# Motor-Y.net
KiCad netlist of a schematic drawn in Altium Designer
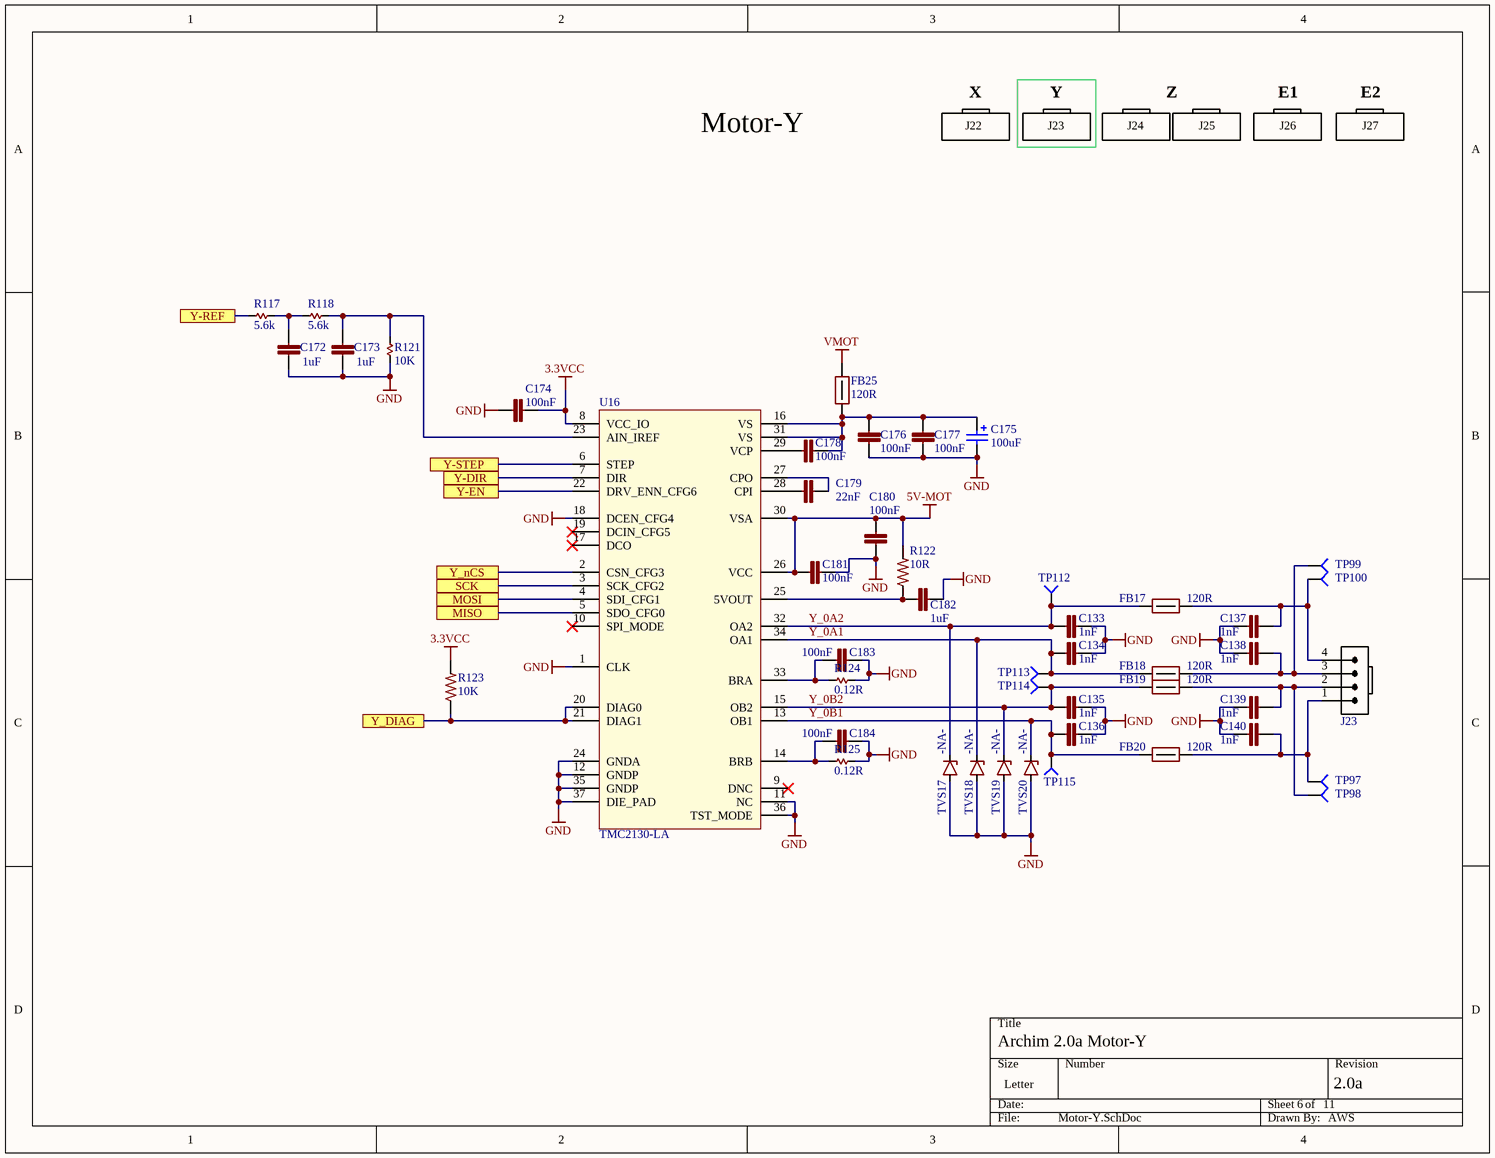
[diagram p0: Motor-Y.SchDoc]

(export (version "E")
  (design (tool "Eeschema 10.0.6"))
  (components
    (comp (ref "C133")
      (value "1nF")
      (footprint "C0402")
      (description "1000pF 50V Ceramic Capacitor X7R 0402 (1005 Metric) 0.039\" L x 0.020\" W (1.00mm x 0.50mm)")
      (fields (field (name "MANUFACTURER") "Murata") (field (name "PART") "1nF 50V X7R 0402"))
      (libsource (lib "3Delight") (part "CAP 1nF 50V 0402 X7R"))
    )
    (comp (ref "C134")
      (value "1nF")
      (footprint "C0402")
      (description "1000pF 50V Ceramic Capacitor X7R 0402 (1005 Metric) 0.039\" L x 0.020\" W (1.00mm x 0.50mm)")
      (fields (field (name "MANUFACTURER") "Murata") (field (name "PART") "1nF 50V X7R 0402"))
      (libsource (lib "3Delight") (part "CAP 1nF 50V 0402 X7R"))
    )
    (comp (ref "C135")
      (value "1nF")
      (footprint "C0402")
      (description "1000pF 50V Ceramic Capacitor X7R 0402 (1005 Metric) 0.039\" L x 0.020\" W (1.00mm x 0.50mm)")
      (fields (field (name "MANUFACTURER") "Murata") (field (name "PART") "1nF 50V X7R 0402"))
      (libsource (lib "3Delight") (part "CAP 1nF 50V 0402 X7R"))
    )
    (comp (ref "C136")
      (value "1nF")
      (footprint "C0402")
      (description "1000pF 50V Ceramic Capacitor X7R 0402 (1005 Metric) 0.039\" L x 0.020\" W (1.00mm x 0.50mm)")
      (fields (field (name "MANUFACTURER") "Murata") (field (name "PART") "1nF 50V X7R 0402"))
      (libsource (lib "3Delight") (part "CAP 1nF 50V 0402 X7R"))
    )
    (comp (ref "C137")
      (value "1nF")
      (footprint "C0402")
      (description "1000pF 50V Ceramic Capacitor X7R 0402 (1005 Metric) 0.039\" L x 0.020\" W (1.00mm x 0.50mm)")
      (fields (field (name "MANUFACTURER") "Murata") (field (name "PART") "1nF 50V X7R 0402"))
      (libsource (lib "") (part "CAP 1nF 50V 0402 X7R_1"))
    )
    (comp (ref "C138")
      (value "1nF")
      (footprint "C0402")
      (description "1000pF 50V Ceramic Capacitor X7R 0402 (1005 Metric) 0.039\" L x 0.020\" W (1.00mm x 0.50mm)")
      (fields (field (name "MANUFACTURER") "Murata") (field (name "PART") "1nF 50V X7R 0402"))
      (libsource (lib "") (part "CAP 1nF 50V 0402 X7R_1"))
    )
    (comp (ref "C139")
      (value "1nF")
      (footprint "C0402")
      (description "1000pF 50V Ceramic Capacitor X7R 0402 (1005 Metric) 0.039\" L x 0.020\" W (1.00mm x 0.50mm)")
      (fields (field (name "MANUFACTURER") "Murata") (field (name "PART") "1nF 50V X7R 0402"))
      (libsource (lib "") (part "CAP 1nF 50V 0402 X7R_1"))
    )
    (comp (ref "C140")
      (value "1nF")
      (footprint "C0402")
      (description "1000pF 50V Ceramic Capacitor X7R 0402 (1005 Metric) 0.039\" L x 0.020\" W (1.00mm x 0.50mm)")
      (fields (field (name "MANUFACTURER") "Murata") (field (name "PART") "1nF 50V X7R 0402"))
      (libsource (lib "") (part "CAP 1nF 50V 0402 X7R_1"))
    )
    (comp (ref "C172")
      (value "1uF")
      (footprint "C0402")
      (description "CAP CER 0402 1uF 6.3V 10% X5R")
      (fields (field (name "MANUFACTURER") "Murata") (field (name "PART") "1uF 6.3V X5R 0402"))
      (libsource (lib "3Delight") (part "GRM155R60J105KE19D"))
    )
    (comp (ref "C173")
      (value "1uF")
      (footprint "C0402")
      (description "CAP CER 0402 1uF 6.3V 10% X5R")
      (fields (field (name "MANUFACTURER") "Murata") (field (name "PART") "1uF 6.3V X5R 0402"))
      (libsource (lib "3Delight") (part "GRM155R60J105KE19D"))
    )
    (comp (ref "C174")
      (value "100nF")
      (footprint "C0402")
      (description "CAP CER 0402 100nF 16V 10% X7R")
      (fields (field (name "MANUFACTURER") "Murata") (field (name "PART") "0.1uF 16V X7R 0402"))
      (libsource (lib "3Delight") (part "GRM155R71C104KA88D"))
    )
    (comp (ref "C175")
      (value "100uF")
      (footprint "CAP-ELEC-063063077")
      (description "CAP ALUM 100UF 35V 20% SMD")
      (fields (field (name "MANUFACTURER") "Nichicon") (field (name "PART") "100uF 35V SMD Al-El"))
      (libsource (lib "3Delight") (part "UWT1V101MCL1GS"))
    )
    (comp (ref "C176")
      (value "100nF")
      (footprint "C0603")
      (description "CAP CER 0603 100nF 50V 10% X7R")
      (fields (field (name "MANUFACTURER") "Kemet") (field (name "PART") "100nF 50V X7R 0603"))
      (libsource (lib "3Delight") (part "C0603C104K5RACTU"))
    )
    (comp (ref "C177")
      (value "100nF")
      (footprint "C0603")
      (description "CAP CER 0603 100nF 50V 10% X7R")
      (fields (field (name "MANUFACTURER") "Kemet") (field (name "PART") "100nF 50V X7R 0603"))
      (libsource (lib "3Delight") (part "C0603C104K5RACTU"))
    )
    (comp (ref "C178")
      (value "100nF")
      (footprint "C0603")
      (description "CAP CER 0603 100nF 50V 10% X7R")
      (fields (field (name "MANUFACTURER") "Kemet") (field (name "PART") "100nF 50V X7R 0603"))
      (libsource (lib "") (part "C0603C104K5RACTU_2"))
    )
    (comp (ref "C179")
      (value "22nF")
      (footprint "C0402")
      (description "CAP CER 0402 22nF ±10% 50V X7R")
      (fields (field (name "MANUFACTURER") "YAGEO") (field (name "TOLERANCE") "+/- 10%"))
      (libsource (lib "3Delight") (part "GCM155R71H223KA55D"))
    )
    (comp (ref "C180")
      (value "100nF")
      (footprint "C0402")
      (description "CAP CER 0402 100nF 16V 10% X7R")
      (fields (field (name "MANUFACTURER") "Murata") (field (name "PART") "0.1uF 16V X7R 0402"))
      (libsource (lib "") (part "GRM155R71C104KA88D_1"))
    )
    (comp (ref "C181")
      (value "100nF")
      (footprint "C0402")
      (description "CAP CER 0402 100nF 16V 10% X7R")
      (fields (field (name "MANUFACTURER") "Murata") (field (name "PART") "0.1uF 16V X7R 0402"))
      (libsource (lib "3Delight") (part "GRM155R71C104KA88D"))
    )
    (comp (ref "C182")
      (value "1uF")
      (footprint "C0402")
      (description "CAP CER 0402 1uF 6.3V 10% X5R")
      (fields (field (name "MANUFACTURER") "Murata") (field (name "PART") "1uF 6.3V X5R 0402"))
      (libsource (lib "") (part "GRM155R60J105KE19D_1"))
    )
    (comp (ref "C183")
      (value "100nF")
      (footprint "C0603")
      (description "CAP CER 0603 100nF 50V 10% X7R")
      (fields (field (name "MANUFACTURER") "Kemet") (field (name "PART") "100nF 50V X7R 0603"))
      (libsource (lib "") (part "C0603C104K5RACTU_1"))
    )
    (comp (ref "C184")
      (value "100nF")
      (footprint "C0603")
      (description "CAP CER 0603 100nF 50V 10% X7R")
      (fields (field (name "MANUFACTURER") "Kemet") (field (name "PART") "100nF 50V X7R 0603"))
      (libsource (lib "") (part "C0603C104K5RACTU_1"))
    )
    (comp (ref "FB17")
      (value "120R")
      (footprint "FB0603")
      (description "FERRITE BEAD 120 OHM 0603 1LN")
      (fields (field (name "MANUFACTURER") "Samsung") (field (name "PART") "FERRITE 120R 3A 0603"))
      (libsource (lib "3Delight") (part "FERRITE 220R 2.5A 0603"))
    )
    (comp (ref "FB18")
      (value "120R")
      (footprint "FB0603")
      (description "FERRITE BEAD 120 OHM 0603 1LN")
      (fields (field (name "MANUFACTURER") "Samsung") (field (name "PART") "FERRITE 120R 3A 0603"))
      (libsource (lib "3Delight") (part "FERRITE 220R 2.5A 0603"))
    )
    (comp (ref "FB19")
      (value "120R")
      (footprint "FB0603")
      (description "FERRITE BEAD 120 OHM 0603 1LN")
      (fields (field (name "MANUFACTURER") "Samsung") (field (name "PART") "FERRITE 120R 3A 0603"))
      (libsource (lib "3Delight") (part "FERRITE 220R 2.5A 0603"))
    )
    (comp (ref "FB20")
      (value "120R")
      (footprint "FB0603")
      (description "FERRITE BEAD 120 OHM 0603 1LN")
      (fields (field (name "MANUFACTURER") "Samsung") (field (name "PART") "FERRITE 120R 3A 0603"))
      (libsource (lib "3Delight") (part "FERRITE 220R 2.5A 0603"))
    )
    (comp (ref "FB25")
      (value "120R")
      (footprint "FB0603")
      (description "FERRITE BEAD 120 OHM 0603 1LN")
      (fields (field (name "MANUFACTURER") "Samsung") (field (name "PART") "FERRITE 120R 3A 0603"))
      (libsource (lib "Inductors") (part "FERRITE 120R 3A 0603"))
    )
    (comp (ref "J23")
      (value "Molex 0705430038")
      (footprint "4POL254 PIN-IN-PASTE")
      (description "Molex 4 Pin Clip Connector - Pin In Paste footprint")
      (libsource (lib "Connectors") (part "Molex 0705430003 PIP"))
    )
    (comp (ref "R117")
      (value "5.6k")
      (footprint "R0402")
      (description "RES SMD 5.6K OHM 1% 1/16W 0402")
      (fields (field (name "MANUFACTURER") "YAGEO") (field (name "TOLERANCE") "1%"))
      (libsource (lib "Resistors") (part "5.6k 1% 0402"))
    )
    (comp (ref "R118")
      (value "5.6k")
      (footprint "R0402")
      (description "RES SMD 5.6K OHM 1% 1/16W 0402")
      (fields (field (name "MANUFACTURER") "YAGEO") (field (name "TOLERANCE") "1%"))
      (libsource (lib "Resistors") (part "5.6k 1% 0402"))
    )
    (comp (ref "R121")
      (value "10K")
      (footprint "R0402")
      (description "RES SMD 10K OHM 1% 1/16W 0402")
      (fields (field (name "MANUFACTURER") "Yageo") (field (name "PART") "10k 1% 0402"))
      (libsource (lib "Resistors") (part "10k 1% 0402"))
    )
    (comp (ref "R122")
      (value "10R")
      (footprint "R0402")
      (description "RES SMD 10 OHM 1% 1/16W 0402")
      (fields (field (name "MANUFACTURER") "Yageo") (field (name "TOLERANCE") "1%"))
      (libsource (lib "3Delight") (part "RC0402FR-0710RL"))
    )
    (comp (ref "R123")
      (value "10K")
      (footprint "R0402")
      (description "RES SMD 10K OHM 1% 1/16W 0402")
      (fields (field (name "MANUFACTURER") "Yageo") (field (name "PART") "10k 1% 0402"))
      (libsource (lib "3Delight") (part "RC0402FR-0710KP"))
    )
    (comp (ref "R124")
      (value "0.12R")
      (footprint "R1206")
      (description "RES 0.12 OHM 1% 1/2W 1206")
      (fields (field (name "TOLERANCE") "+/- 1%"))
      (libsource (lib "Resistors") (part "0.12R 1% 1206"))
    )
    (comp (ref "R125")
      (value "0.12R")
      (footprint "R1206")
      (description "RES 0.12 OHM 1% 1/2W 1206")
      (fields (field (name "TOLERANCE") "+/- 1%"))
      (libsource (lib "Resistors") (part "0.12R 1% 1206"))
    )
    (comp (ref "TP97")
      (value "TP4")
      (footprint "TP-2")
      (description "Socket")
      (libsource (lib "Archim") (part "Socket"))
    )
    (comp (ref "TP98")
      (value "TP4")
      (footprint "TP-2")
      (description "Socket")
      (libsource (lib "Archim") (part "Socket"))
    )
    (comp (ref "TP99")
      (value "TP4")
      (footprint "TP-2")
      (description "Socket")
      (libsource (lib "Archim") (part "Socket"))
    )
    (comp (ref "TP100")
      (value "TP4")
      (footprint "TP-2")
      (description "Socket")
      (libsource (lib "Archim") (part "Socket"))
    )
    (comp (ref "TP112")
      (value "TP4")
      (footprint "TP-2")
      (description "Socket")
      (libsource (lib "Archim") (part "Socket"))
    )
    (comp (ref "TP113")
      (value "TP4")
      (footprint "TP-2")
      (description "Socket")
      (libsource (lib "Archim") (part "Socket"))
    )
    (comp (ref "TP114")
      (value "TP4")
      (footprint "TP-2")
      (description "Socket")
      (libsource (lib "Archim") (part "Socket"))
    )
    (comp (ref "TP115")
      (value "TP4")
      (footprint "TP-2")
      (description "Socket")
      (libsource (lib "Archim") (part "Socket"))
    )
    (comp (ref "TVS17")
      (value "-NA-")
      (footprint "SMF")
      (description "TVS DIODE 30VWM 48.4VC SMF")
      (fields (field (name "MANUFACTURER") "Vishay") (field (name "PART") "TVS Diode 48.4VC"))
      (libsource (lib "3Delight") (part "TVS 30V SMF"))
    )
    (comp (ref "TVS18")
      (value "-NA-")
      (footprint "SMF")
      (description "TVS DIODE 30VWM 48.4VC SMF")
      (fields (field (name "MANUFACTURER") "Vishay") (field (name "PART") "TVS Diode 48.4VC"))
      (libsource (lib "3Delight") (part "TVS 30V SMF"))
    )
    (comp (ref "TVS19")
      (value "-NA-")
      (footprint "SMF")
      (description "TVS DIODE 30VWM 48.4VC SMF")
      (fields (field (name "MANUFACTURER") "Vishay") (field (name "PART") "TVS Diode 48.4VC"))
      (libsource (lib "3Delight") (part "TVS 30V SMF"))
    )
    (comp (ref "TVS20")
      (value "-NA-")
      (footprint "SMF")
      (description "TVS DIODE 30VWM 48.4VC SMF")
      (fields (field (name "MANUFACTURER") "Vishay") (field (name "PART") "TVS Diode 48.4VC"))
      (libsource (lib "3Delight") (part "TVS 30V SMF"))
    )
    (comp (ref "U16")
      (value "TMC2130-LA")
      (footprint "QFN36-50P500X600X900_HS-37N")
      (description "IC STEPPER MOTOR DVR SPI 36QFN")
      (fields (field (name "MANUFACTURER") "Trinamic") (field (name "PART") "TMC2130"))
      (libsource (lib "ICs-Motor Controller") (part "TMC2130-LA-T"))
    )
  )
  (nets
    (net (code "1") (name "/MISO") (class "Default")
      (node (ref "U16") (pin "5") (pinfunction "SDO_CFG0_5") (pintype "passive"))
    )
    (net (code "2") (name "/MOSI") (class "Default")
      (node (ref "U16") (pin "4") (pinfunction "SDI_CFG1_4") (pintype "passive"))
    )
    (net (code "3") (name "/SCK") (class "Default")
      (node (ref "U16") (pin "3") (pinfunction "SCK_CFG2_3") (pintype "passive"))
    )
    (net (code "4") (name "/Y-DIR") (class "Default")
      (node (ref "U16") (pin "7") (pinfunction "DIR_7") (pintype "passive"))
    )
    (net (code "5") (name "/Y-EN") (class "Default")
      (node (ref "U16") (pin "22") (pinfunction "DRV_ENN_CFG6_22") (pintype "passive"))
    )
    (net (code "6") (name "/Y-REF") (class "Default")
      (node (ref "R117") (pin "1") (pinfunction "1_1") (pintype "passive"))
    )
    (net (code "7") (name "/Y-STEP") (class "Default")
      (node (ref "U16") (pin "6") (pinfunction "STEP_6") (pintype "passive"))
    )
    (net (code "8") (name "/Y_0A1") (class "Default")
      (node (ref "C134") (pin "1") (pinfunction "1_1") (pintype "passive"))
      (node (ref "FB18") (pin "1") (pinfunction "1_1") (pintype "passive"))
      (node (ref "TP113") (pin "1") (pinfunction "1_1") (pintype "passive"))
      (node (ref "TVS18") (pin "K") (pinfunction "K_K") (pintype "passive"))
      (node (ref "U16") (pin "34") (pinfunction "OA1_34") (pintype "passive"))
    )
    (net (code "9") (name "/Y_0A2") (class "Default")
      (node (ref "C133") (pin "1") (pinfunction "1_1") (pintype "passive"))
      (node (ref "FB17") (pin "1") (pinfunction "1_1") (pintype "passive"))
      (node (ref "TP112") (pin "1") (pinfunction "1_1") (pintype "passive"))
      (node (ref "TVS17") (pin "K") (pinfunction "K_K") (pintype "passive"))
      (node (ref "U16") (pin "32") (pinfunction "OA2_32") (pintype "passive"))
    )
    (net (code "10") (name "/Y_0B1") (class "Default")
      (node (ref "C136") (pin "1") (pinfunction "1_1") (pintype "passive"))
      (node (ref "FB20") (pin "1") (pinfunction "1_1") (pintype "passive"))
      (node (ref "TP115") (pin "1") (pinfunction "1_1") (pintype "passive"))
      (node (ref "TVS20") (pin "K") (pinfunction "K_K") (pintype "passive"))
      (node (ref "U16") (pin "13") (pinfunction "OB1_13") (pintype "passive"))
    )
    (net (code "11") (name "/Y_0B2") (class "Default")
      (node (ref "C135") (pin "1") (pinfunction "1_1") (pintype "passive"))
      (node (ref "FB19") (pin "1") (pinfunction "1_1") (pintype "passive"))
      (node (ref "TP114") (pin "1") (pinfunction "1_1") (pintype "passive"))
      (node (ref "TVS19") (pin "K") (pinfunction "K_K") (pintype "passive"))
      (node (ref "U16") (pin "15") (pinfunction "OB2_15") (pintype "passive"))
    )
    (net (code "12") (name "/Y_DIAG") (class "Default")
      (node (ref "R123") (pin "1") (pinfunction "1_1") (pintype "passive"))
      (node (ref "U16") (pin "20") (pinfunction "DIAG0_20") (pintype "passive"))
      (node (ref "U16") (pin "21") (pinfunction "DIAG1_21") (pintype "passive"))
    )
    (net (code "13") (name "/Y_nCS") (class "Default")
      (node (ref "U16") (pin "2") (pinfunction "CSN_CFG3_2") (pintype "passive"))
    )
    (net (code "14") (name "3.3VCC") (class "Default")
      (node (ref "C174") (pin "1") (pinfunction "1_1") (pintype "passive"))
      (node (ref "R123") (pin "2") (pinfunction "2_2") (pintype "passive"))
      (node (ref "U16") (pin "8") (pinfunction "VCC_IO_8") (pintype "passive"))
    )
    (net (code "15") (name "5V-MOT") (class "Default")
      (node (ref "C180") (pin "2") (pinfunction "2_2") (pintype "passive"))
      (node (ref "C181") (pin "2") (pinfunction "2_2") (pintype "passive"))
      (node (ref "R122") (pin "2") (pinfunction "2_2") (pintype "passive"))
      (node (ref "U16") (pin "26") (pinfunction "VCC_26") (pintype "passive"))
      (node (ref "U16") (pin "30") (pinfunction "VSA_30") (pintype "passive"))
    )
    (net (code "16") (name "GND") (class "Default")
      (node (ref "C133") (pin "2") (pinfunction "2_2") (pintype "passive"))
      (node (ref "C134") (pin "2") (pinfunction "2_2") (pintype "passive"))
      (node (ref "C135") (pin "2") (pinfunction "2_2") (pintype "passive"))
      (node (ref "C136") (pin "2") (pinfunction "2_2") (pintype "passive"))
      (node (ref "C137") (pin "2") (pinfunction "2_2") (pintype "passive"))
      (node (ref "C138") (pin "2") (pinfunction "2_2") (pintype "passive"))
      (node (ref "C139") (pin "2") (pinfunction "2_2") (pintype "passive"))
      (node (ref "C140") (pin "2") (pinfunction "2_2") (pintype "passive"))
      (node (ref "C172") (pin "2") (pinfunction "2_2") (pintype "passive"))
      (node (ref "C173") (pin "2") (pinfunction "2_2") (pintype "passive"))
      (node (ref "C174") (pin "2") (pinfunction "2_2") (pintype "passive"))
      (node (ref "C175") (pin "2") (pinfunction "2_2") (pintype "passive"))
      (node (ref "C176") (pin "1") (pinfunction "1_1") (pintype "passive"))
      (node (ref "C177") (pin "1") (pinfunction "1_1") (pintype "passive"))
      (node (ref "C180") (pin "1") (pinfunction "1_1") (pintype "passive"))
      (node (ref "C181") (pin "1") (pinfunction "1_1") (pintype "passive"))
      (node (ref "C182") (pin "2") (pinfunction "2_2") (pintype "passive"))
      (node (ref "C183") (pin "1") (pinfunction "1_1") (pintype "passive"))
      (node (ref "C184") (pin "1") (pinfunction "1_1") (pintype "passive"))
      (node (ref "R121") (pin "1") (pinfunction "1_1") (pintype "passive"))
      (node (ref "R124") (pin "2") (pinfunction "2_2") (pintype "passive"))
      (node (ref "R125") (pin "2") (pinfunction "2_2") (pintype "passive"))
      (node (ref "TVS17") (pin "A") (pinfunction "A_A") (pintype "passive"))
      (node (ref "TVS18") (pin "A") (pinfunction "A_A") (pintype "passive"))
      (node (ref "TVS19") (pin "A") (pinfunction "A_A") (pintype "passive"))
      (node (ref "TVS20") (pin "A") (pinfunction "A_A") (pintype "passive"))
      (node (ref "U16") (pin "1") (pinfunction "CLK_1") (pintype "passive"))
      (node (ref "U16") (pin "11") (pinfunction "NC_11") (pintype "passive"))
      (node (ref "U16") (pin "12") (pinfunction "GNDP_12") (pintype "passive"))
      (node (ref "U16") (pin "18") (pinfunction "DCEN_CFG4_18") (pintype "passive"))
      (node (ref "U16") (pin "24") (pinfunction "GNDA_24") (pintype "passive"))
      (node (ref "U16") (pin "35") (pinfunction "GNDP_35") (pintype "passive"))
      (node (ref "U16") (pin "36") (pinfunction "TST_MODE_36") (pintype "passive"))
      (node (ref "U16") (pin "37") (pinfunction "DIE_PAD_37") (pintype "passive"))
    )
    (net (code "17") (name "Net-(C137-Pad1)") (class "Default")
      (node (ref "C137") (pin "1") (pinfunction "1_1") (pintype "passive"))
      (node (ref "FB17") (pin "2") (pinfunction "2_2") (pintype "passive"))
      (node (ref "J23") (pin "4") (pinfunction "4_4") (pintype "passive"))
      (node (ref "TP100") (pin "1") (pinfunction "1_1") (pintype "passive"))
    )
    (net (code "18") (name "Net-(C138-Pad1)") (class "Default")
      (node (ref "C138") (pin "1") (pinfunction "1_1") (pintype "passive"))
      (node (ref "FB18") (pin "2") (pinfunction "2_2") (pintype "passive"))
      (node (ref "J23") (pin "3") (pinfunction "3_3") (pintype "passive"))
      (node (ref "TP99") (pin "1") (pinfunction "1_1") (pintype "passive"))
    )
    (net (code "19") (name "Net-(C139-Pad1)") (class "Default")
      (node (ref "C139") (pin "1") (pinfunction "1_1") (pintype "passive"))
      (node (ref "FB19") (pin "2") (pinfunction "2_2") (pintype "passive"))
      (node (ref "J23") (pin "2") (pinfunction "2_2") (pintype "passive"))
      (node (ref "TP98") (pin "1") (pinfunction "1_1") (pintype "passive"))
    )
    (net (code "20") (name "Net-(C140-Pad1)") (class "Default")
      (node (ref "C140") (pin "1") (pinfunction "1_1") (pintype "passive"))
      (node (ref "FB20") (pin "2") (pinfunction "2_2") (pintype "passive"))
      (node (ref "J23") (pin "1") (pinfunction "1_1") (pintype "passive"))
      (node (ref "TP97") (pin "1") (pinfunction "1_1") (pintype "passive"))
    )
    (net (code "21") (name "Net-(C172-Pad1)") (class "Default")
      (node (ref "C172") (pin "1") (pinfunction "1_1") (pintype "passive"))
      (node (ref "R117") (pin "2") (pinfunction "2_2") (pintype "passive"))
      (node (ref "R118") (pin "1") (pinfunction "1_1") (pintype "passive"))
    )
    (net (code "22") (name "Net-(C175-Pad1)") (class "Default")
      (node (ref "C175") (pin "1") (pinfunction "1_1") (pintype "passive"))
      (node (ref "C176") (pin "2") (pinfunction "2_2") (pintype "passive"))
      (node (ref "C177") (pin "2") (pinfunction "2_2") (pintype "passive"))
      (node (ref "C178") (pin "2") (pinfunction "2_2") (pintype "passive"))
      (node (ref "FB25") (pin "1") (pinfunction "1_1") (pintype "passive"))
      (node (ref "U16") (pin "16") (pinfunction "VS_16") (pintype "passive"))
      (node (ref "U16") (pin "31") (pinfunction "VS_31") (pintype "passive"))
    )
    (net (code "23") (name "Net-(U16-5VOUT)") (class "Default")
      (node (ref "C182") (pin "1") (pinfunction "1_1") (pintype "passive"))
      (node (ref "R122") (pin "1") (pinfunction "1_1") (pintype "passive"))
      (node (ref "U16") (pin "25") (pinfunction "5VOUT_25") (pintype "passive"))
    )
    (net (code "24") (name "Net-(U16-AIN_IREF)") (class "Default")
      (node (ref "C173") (pin "1") (pinfunction "1_1") (pintype "passive"))
      (node (ref "R118") (pin "2") (pinfunction "2_2") (pintype "passive"))
      (node (ref "R121") (pin "2") (pinfunction "2_2") (pintype "passive"))
      (node (ref "U16") (pin "23") (pinfunction "AIN_IREF_23") (pintype "passive"))
    )
    (net (code "25") (name "Net-(U16-BRA)") (class "Default")
      (node (ref "C183") (pin "2") (pinfunction "2_2") (pintype "passive"))
      (node (ref "R124") (pin "1") (pinfunction "1_1") (pintype "passive"))
      (node (ref "U16") (pin "33") (pinfunction "BRA_33") (pintype "passive"))
    )
    (net (code "26") (name "Net-(U16-BRB)") (class "Default")
      (node (ref "C184") (pin "2") (pinfunction "2_2") (pintype "passive"))
      (node (ref "R125") (pin "1") (pinfunction "1_1") (pintype "passive"))
      (node (ref "U16") (pin "14") (pinfunction "BRB_14") (pintype "passive"))
    )
    (net (code "27") (name "Net-(U16-CPI)") (class "Default")
      (node (ref "C179") (pin "1") (pinfunction "1_1") (pintype "passive"))
      (node (ref "U16") (pin "28") (pinfunction "CPI_28") (pintype "passive"))
    )
    (net (code "28") (name "Net-(U16-CPO)") (class "Default")
      (node (ref "C179") (pin "2") (pinfunction "2_2") (pintype "passive"))
      (node (ref "U16") (pin "27") (pinfunction "CPO_27") (pintype "passive"))
    )
    (net (code "29") (name "Net-(U16-VCP)") (class "Default")
      (node (ref "C178") (pin "1") (pinfunction "1_1") (pintype "passive"))
      (node (ref "U16") (pin "29") (pinfunction "VCP_29") (pintype "passive"))
    )
    (net (code "30") (name "VMOT") (class "Default")
      (node (ref "FB25") (pin "2") (pinfunction "2_2") (pintype "passive"))
    )
    (net (code "31") (name "unconnected-(U16-DCIN_CFG5-Pad19)") (class "Default")
      (node (ref "U16") (pin "19") (pinfunction "DCIN_CFG5_19") (pintype "passive+no_connect"))
    )
    (net (code "32") (name "unconnected-(U16-DCO-Pad17)") (class "Default")
      (node (ref "U16") (pin "17") (pinfunction "DCO_17") (pintype "passive+no_connect"))
    )
    (net (code "33") (name "unconnected-(U16-DNC-Pad9)") (class "Default")
      (node (ref "U16") (pin "9") (pinfunction "DNC_9") (pintype "passive+no_connect"))
    )
    (net (code "34") (name "unconnected-(U16-SPI_MODE-Pad10)") (class "Default")
      (node (ref "U16") (pin "10") (pinfunction "SPI_MODE_10") (pintype "passive+no_connect"))
    )
  )
)
